# power_electronics2.net
KiCad netlist of a schematic drawn in EAGLE
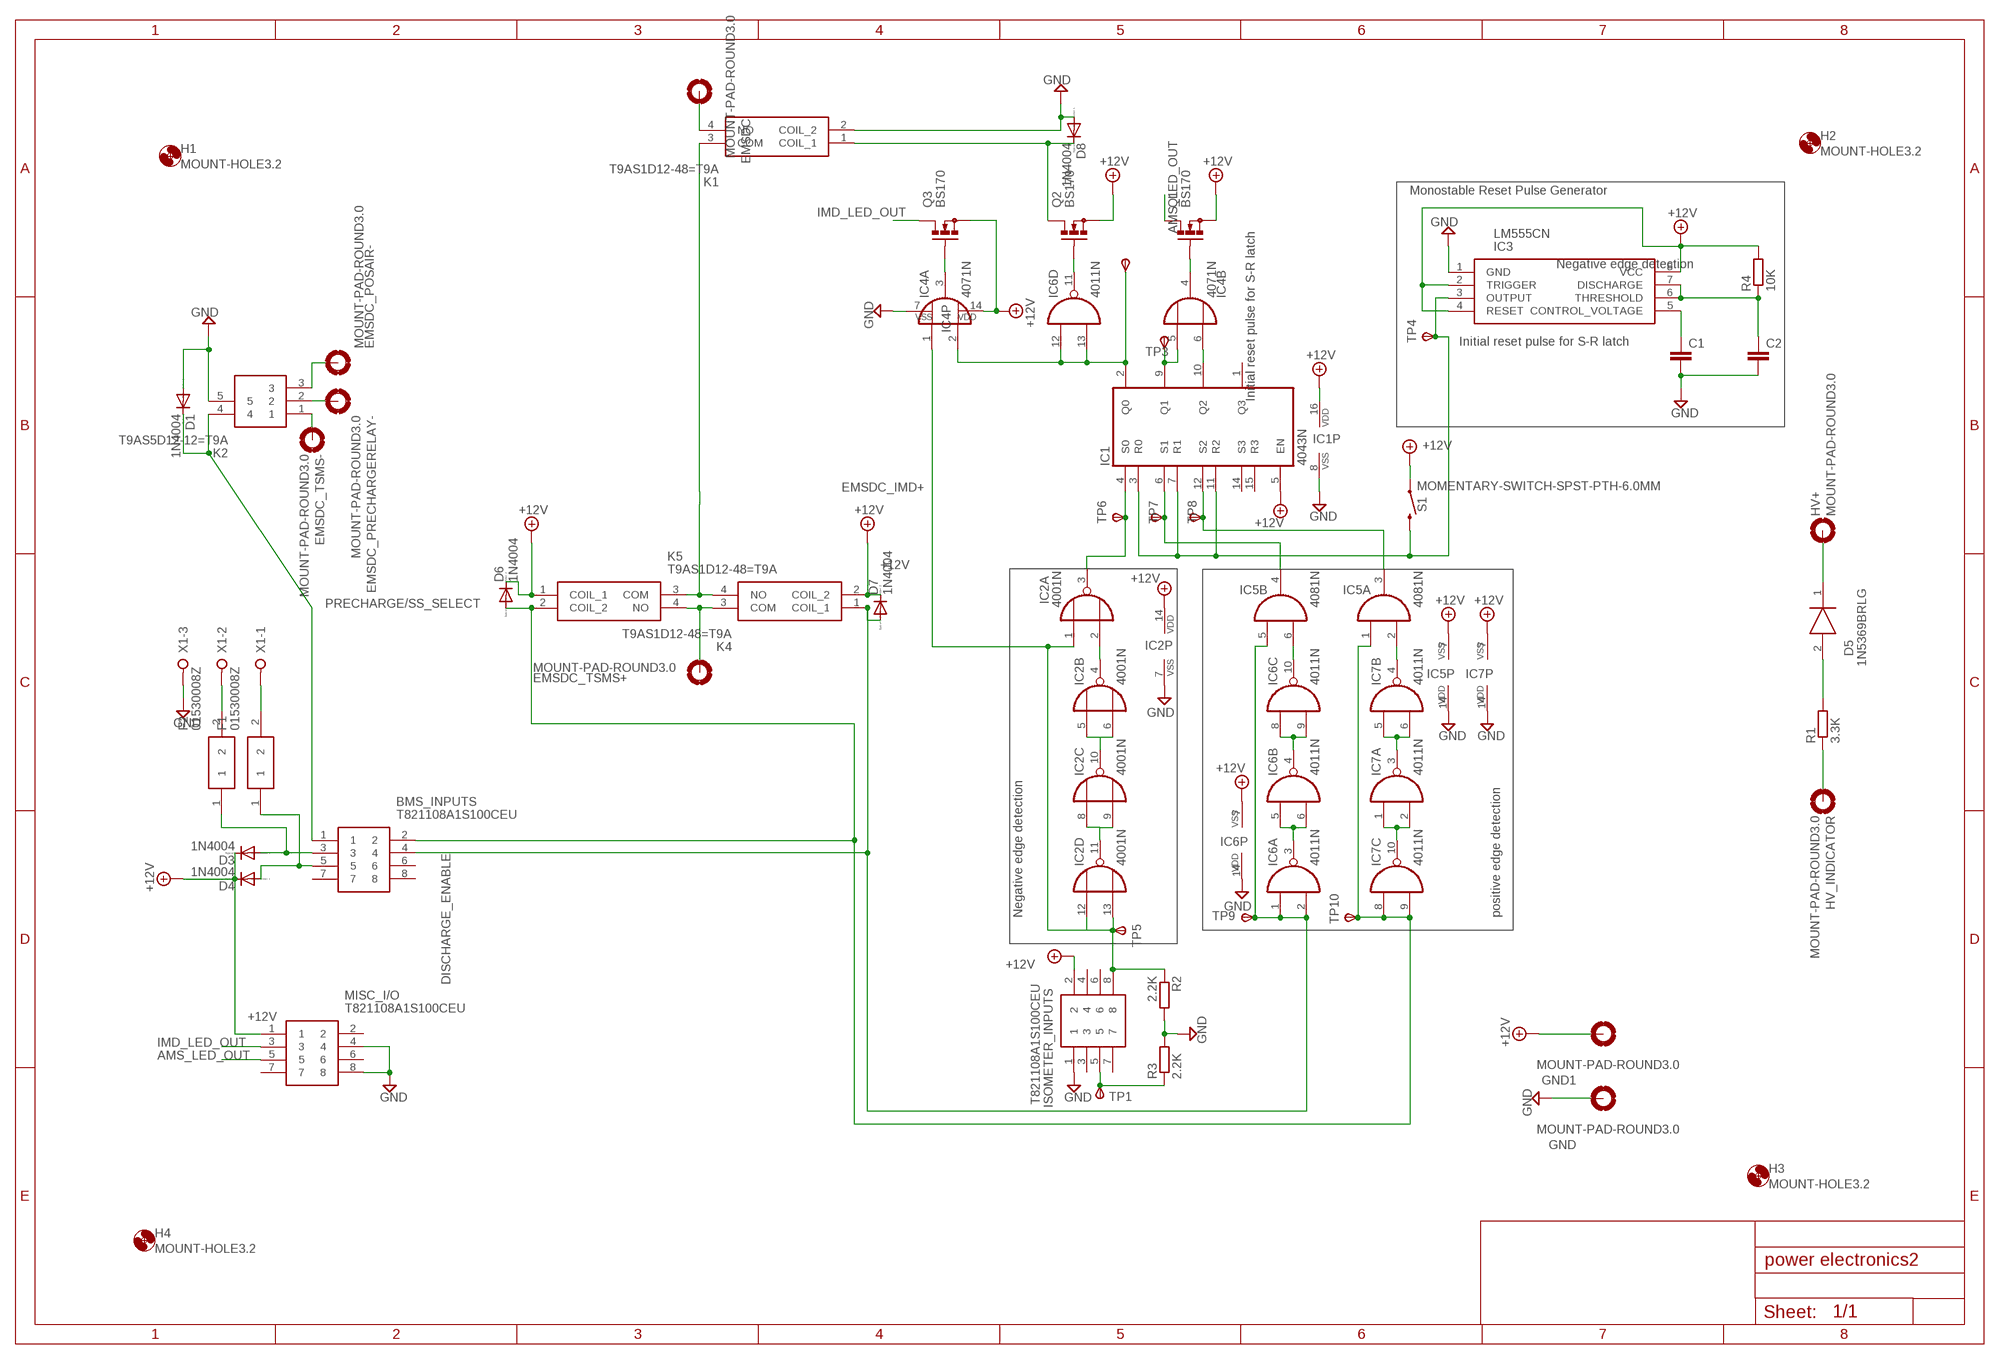
[diagram p0: schematic, sheet 1]

(export (version "E")
  (design (tool "Eeschema 10.0.6"))
  (components
    (comp (ref "BMS_INPUTS")
      (value "T821108A1S100CEU")
      (footprint "eagle-import:HDRV8W64P254_2X4_1778X895X915P")
      (fields (field (name "RS_PART_NUMBER") "8323569"))
      (libsource (lib "eagle-import") (part "T821108A1S100CEU"))
    )
    (comp (ref "C1")
      (value "C-EU050-024X044")
      (footprint "eagle-import:C050-024X044")
      (libsource (lib "eagle-import") (part "C-EU050-024X044"))
    )
    (comp (ref "C2")
      (value "C-EU050-024X044")
      (footprint "eagle-import:C050-024X044")
      (libsource (lib "eagle-import") (part "C-EU050-024X044"))
    )
    (comp (ref "D1")
      (value "1N4004")
      (footprint "eagle-import:DO41-10")
      (libsource (lib "eagle-import") (part "1N4004"))
    )
    (comp (ref "D3")
      (value "1N4004")
      (footprint "eagle-import:DO41-10")
      (libsource (lib "eagle-import") (part "1N4004"))
    )
    (comp (ref "D4")
      (value "1N4004")
      (footprint "eagle-import:DO41-10")
      (libsource (lib "eagle-import") (part "1N4004"))
    )
    (comp (ref "D5")
      (value "1N5369BRLG")
      (footprint "eagle-import:DIOAD2260W109L864D349")
      (fields (field (name "RS_PART_NUMBER") "6547678P"))
      (libsource (lib "eagle-import") (part "1N5369BRLG"))
    )
    (comp (ref "D6")
      (value "1N4004")
      (footprint "eagle-import:DO41-10")
      (libsource (lib "eagle-import") (part "1N4004"))
    )
    (comp (ref "D7")
      (value "1N4004")
      (footprint "eagle-import:DO41-10")
      (libsource (lib "eagle-import") (part "1N4004"))
    )
    (comp (ref "D8")
      (value "1N4004")
      (footprint "eagle-import:DO41-10")
      (libsource (lib "eagle-import") (part "1N4004"))
    )
    (comp (ref "EMSDC")
      (value "MOUNT-PAD-ROUND3.0")
      (footprint "eagle-import:3,0-PAD")
      (libsource (lib "eagle-import") (part "MOUNT-PAD-ROUND3.0"))
    )
    (comp (ref "EMSDC_POSAIR-")
      (value "MOUNT-PAD-ROUND3.0")
      (footprint "eagle-import:3,0-PAD")
      (libsource (lib "eagle-import") (part "MOUNT-PAD-ROUND3.0"))
    )
    (comp (ref "EMSDC_PRECHARGERELAY-")
      (value "MOUNT-PAD-ROUND3.0")
      (footprint "eagle-import:3,0-PAD")
      (libsource (lib "eagle-import") (part "MOUNT-PAD-ROUND3.0"))
    )
    (comp (ref "EMSDC_TSMS+")
      (value "MOUNT-PAD-ROUND3.0")
      (footprint "eagle-import:3,0-PAD")
      (libsource (lib "eagle-import") (part "MOUNT-PAD-ROUND3.0"))
    )
    (comp (ref "EMSDC_TSMS-")
      (value "MOUNT-PAD-ROUND3.0")
      (footprint "eagle-import:3,0-PAD")
      (libsource (lib "eagle-import") (part "MOUNT-PAD-ROUND3.0"))
    )
    (comp (ref "F1")
      (value "01530008Z")
      (footprint "eagle-import:01530008")
      (fields (field (name "RS_PART_NUMBER") "3607317"))
      (libsource (lib "eagle-import") (part "01530008Z"))
    )
    (comp (ref "F2")
      (value "01530008Z")
      (footprint "eagle-import:01530008")
      (fields (field (name "RS_PART_NUMBER") "3607317"))
      (libsource (lib "eagle-import") (part "01530008Z"))
    )
    (comp (ref "GND")
      (value "MOUNT-PAD-ROUND3.0")
      (footprint "eagle-import:3,0-PAD")
      (libsource (lib "eagle-import") (part "MOUNT-PAD-ROUND3.0"))
    )
    (comp (ref "GND1")
      (value "MOUNT-PAD-ROUND3.0")
      (footprint "eagle-import:3,0-PAD")
      (libsource (lib "eagle-import") (part "MOUNT-PAD-ROUND3.0"))
    )
    (comp (ref "H1")
      (value "MOUNT-HOLE3.2")
      (footprint "eagle-import:3,2")
      (libsource (lib "eagle-import") (part "MOUNT-HOLE3.2"))
    )
    (comp (ref "H2")
      (value "MOUNT-HOLE3.2")
      (footprint "eagle-import:3,2")
      (libsource (lib "eagle-import") (part "MOUNT-HOLE3.2"))
    )
    (comp (ref "H3")
      (value "MOUNT-HOLE3.2")
      (footprint "eagle-import:3,2")
      (libsource (lib "eagle-import") (part "MOUNT-HOLE3.2"))
    )
    (comp (ref "H4")
      (value "MOUNT-HOLE3.2")
      (footprint "eagle-import:3,2")
      (libsource (lib "eagle-import") (part "MOUNT-HOLE3.2"))
    )
    (comp (ref "HV+")
      (value "MOUNT-PAD-ROUND3.0")
      (footprint "eagle-import:3,0-PAD")
      (libsource (lib "eagle-import") (part "MOUNT-PAD-ROUND3.0"))
    )
    (comp (ref "HV_INDICATOR")
      (value "MOUNT-PAD-ROUND3.0")
      (footprint "eagle-import:3,0-PAD")
      (libsource (lib "eagle-import") (part "MOUNT-PAD-ROUND3.0"))
    )
    (comp (ref "IC1")
      (value "4043N")
      (footprint "eagle-import:DIL16")
      (libsource (lib "eagle-import") (part "4043N"))
    )
    (comp (ref "IC2")
      (value "4001N")
      (footprint "eagle-import:DIL14")
      (libsource (lib "eagle-import") (part "4001N"))
    )
    (comp (ref "IC3")
      (value "LM555CN")
      (footprint "eagle-import:DIP762W53P254L980H533Q8N")
      (fields (field (name "MOUSER_PART_NUMBER") "512-LM555CN"))
      (libsource (lib "eagle-import") (part "LM555CN"))
    )
    (comp (ref "IC4")
      (value "4071N")
      (footprint "eagle-import:DIL14")
      (libsource (lib "eagle-import") (part "4071N"))
    )
    (comp (ref "IC5")
      (value "4081N")
      (footprint "eagle-import:DIL14")
      (libsource (lib "eagle-import") (part "4081N"))
    )
    (comp (ref "IC6")
      (value "4011N")
      (footprint "eagle-import:DIL14")
      (libsource (lib "eagle-import") (part "4011N"))
    )
    (comp (ref "IC7")
      (value "4011N")
      (footprint "eagle-import:DIL14")
      (libsource (lib "eagle-import") (part "4011N"))
    )
    (comp (ref "ISOMETER_INPUTS")
      (value "T821108A1S100CEU")
      (footprint "eagle-import:HDRV8W64P254_2X4_1778X895X915P")
      (fields (field (name "RS_PART_NUMBER") "8323569"))
      (libsource (lib "eagle-import") (part "T821108A1S100CEU"))
    )
    (comp (ref "K1")
      (value "T9AS1D12-48=T9A")
      (footprint "eagle-import:T9AS1D1248T9A")
      (fields (field (name "RS_PART_NUMBER") "6802534P"))
      (libsource (lib "eagle-import") (part "T9AS1D12-48=T9A"))
    )
    (comp (ref "K2")
      (value "T9AS5D12-12=T9A")
      (footprint "eagle-import:T9AS1D12")
      (fields (field (name "RS_PART_NUMBER") "6802528"))
      (libsource (lib "eagle-import") (part "T9AS5D12-12=T9A"))
    )
    (comp (ref "K4")
      (value "T9AS1D12-48=T9A")
      (footprint "eagle-import:T9AS1D1248T9A")
      (fields (field (name "RS_PART_NUMBER") "6802534P"))
      (libsource (lib "eagle-import") (part "T9AS1D12-48=T9A"))
    )
    (comp (ref "K5")
      (value "T9AS1D12-48=T9A")
      (footprint "eagle-import:T9AS1D1248T9A")
      (fields (field (name "RS_PART_NUMBER") "6802534P"))
      (libsource (lib "eagle-import") (part "T9AS1D12-48=T9A"))
    )
    (comp (ref "MISC_I/O")
      (value "T821108A1S100CEU")
      (footprint "eagle-import:HDRV8W64P254_2X4_1778X895X915P")
      (fields (field (name "RS_PART_NUMBER") "8323569"))
      (libsource (lib "eagle-import") (part "T821108A1S100CEU"))
    )
    (comp (ref "Q1")
      (value "BS170")
      (footprint "eagle-import:SOT54E")
      (libsource (lib "eagle-import") (part "BS170"))
    )
    (comp (ref "Q2")
      (value "BS170")
      (footprint "eagle-import:SOT54E")
      (libsource (lib "eagle-import") (part "BS170"))
    )
    (comp (ref "Q3")
      (value "BS170")
      (footprint "eagle-import:SOT54E")
      (libsource (lib "eagle-import") (part "BS170"))
    )
    (comp (ref "R1")
      (value "3.3K")
      (footprint "eagle-import:0207_15")
      (libsource (lib "eagle-import") (part "R-EU_0207/15"))
    )
    (comp (ref "R2")
      (value "2.2K")
      (footprint "eagle-import:0207_12")
      (libsource (lib "eagle-import") (part "R-EU_0207/12"))
    )
    (comp (ref "R3")
      (value "2.2K")
      (footprint "eagle-import:0207_12")
      (libsource (lib "eagle-import") (part "R-EU_0207/12"))
    )
    (comp (ref "R4")
      (value "10K")
      (footprint "eagle-import:0207_15")
      (libsource (lib "eagle-import") (part "R-EU_0207/15"))
    )
    (comp (ref "S1")
      (value "MOMENTARY-SWITCH-SPST-PTH-6.0MM")
      (footprint "eagle-import:TACTILE_SWITCH_PTH_6.0MM")
      (libsource (lib "eagle-import") (part "MOMENTARY-SWITCH-SPST-PTH-6.0MM"))
    )
    (comp (ref "TP1")
      (value "TPSPAD1-17")
      (footprint "eagle-import:P1-17")
      (libsource (lib "eagle-import") (part "TPSPAD1-17"))
    )
    (comp (ref "TP2")
      (value "TPSPAD1-17")
      (footprint "eagle-import:P1-17")
      (libsource (lib "eagle-import") (part "TPSPAD1-17"))
    )
    (comp (ref "TP3")
      (value "TPSPAD1-17")
      (footprint "eagle-import:P1-17")
      (libsource (lib "eagle-import") (part "TPSPAD1-17"))
    )
    (comp (ref "TP4")
      (value "TPSPAD1-17")
      (footprint "eagle-import:P1-17")
      (libsource (lib "eagle-import") (part "TPSPAD1-17"))
    )
    (comp (ref "TP5")
      (value "TPSPAD1-17")
      (footprint "eagle-import:P1-17")
      (libsource (lib "eagle-import") (part "TPSPAD1-17"))
    )
    (comp (ref "TP6")
      (value "TPSPAD1-17")
      (footprint "eagle-import:P1-17")
      (libsource (lib "eagle-import") (part "TPSPAD1-17"))
    )
    (comp (ref "TP7")
      (value "TPSPAD1-17")
      (footprint "eagle-import:P1-17")
      (libsource (lib "eagle-import") (part "TPSPAD1-17"))
    )
    (comp (ref "TP8")
      (value "TPSPAD1-17")
      (footprint "eagle-import:P1-17")
      (libsource (lib "eagle-import") (part "TPSPAD1-17"))
    )
    (comp (ref "TP9")
      (value "TPSPAD1-17")
      (footprint "eagle-import:P1-17")
      (libsource (lib "eagle-import") (part "TPSPAD1-17"))
    )
    (comp (ref "TP10")
      (value "TPSPAD1-17")
      (footprint "eagle-import:P1-17")
      (libsource (lib "eagle-import") (part "TPSPAD1-17"))
    )
    (comp (ref "X1")
      (value "W237-3E")
      (footprint "eagle-import:W237-3E")
      (libsource (lib "eagle-import") (part "W237-3E"))
    )
  )
  (nets
    (net (code "1") (name "+12V") (class "Default")
      (node (ref "D3") (pin "C") (pinfunction "C_C") (pintype "passive"))
      (node (ref "D4") (pin "C") (pinfunction "C_C") (pintype "passive"))
      (node (ref "D6") (pin "C") (pinfunction "C_C") (pintype "passive"))
      (node (ref "D7") (pin "C") (pinfunction "C_C") (pintype "passive"))
      (node (ref "GND1") (pin "B3,0") (pinfunction "MOUNT_B3,0") (pintype "passive"))
      (node (ref "IC1") (pin "16") (pinfunction "VDD_16") (pintype "power_in"))
      (node (ref "IC1") (pin "5") (pinfunction "EN_5") (pintype "input"))
      (node (ref "IC2") (pin "14") (pinfunction "VDD_14") (pintype "power_in"))
      (node (ref "IC3") (pin "2") (pinfunction "TRIGGER_2") (pintype "bidirectional"))
      (node (ref "IC3") (pin "4") (pinfunction "RESET_4") (pintype "bidirectional"))
      (node (ref "IC3") (pin "8") (pinfunction "VCC_8") (pintype "bidirectional"))
      (node (ref "IC4") (pin "14") (pinfunction "VDD_14") (pintype "power_in"))
      (node (ref "IC5") (pin "7") (pinfunction "VSS_7") (pintype "power_in"))
      (node (ref "IC6") (pin "7") (pinfunction "VSS_7") (pintype "power_in"))
      (node (ref "IC7") (pin "7") (pinfunction "VSS_7") (pintype "power_in"))
      (node (ref "ISOMETER_INPUTS") (pin "2") (pinfunction "2_2") (pintype "bidirectional"))
      (node (ref "K4") (pin "2") (pinfunction "COIL_2_2") (pintype "bidirectional"))
      (node (ref "K5") (pin "1") (pinfunction "COIL_1_1") (pintype "bidirectional"))
      (node (ref "MISC_I/O") (pin "1") (pinfunction "1_1") (pintype "bidirectional"))
      (node (ref "Q1") (pin "S") (pinfunction "S_S") (pintype "passive"))
      (node (ref "Q2") (pin "S") (pinfunction "S_S") (pintype "passive"))
      (node (ref "Q3") (pin "S") (pinfunction "S_S") (pintype "passive"))
      (node (ref "R4") (pin "2") (pinfunction "2_2") (pintype "passive"))
      (node (ref "S1") (pin "1") (pinfunction "1_1") (pintype "passive"))
    )
    (net (code "2") (name "/AMS_LED_OUT") (class "Default")
      (node (ref "MISC_I/O") (pin "5") (pinfunction "5_5") (pintype "bidirectional"))
      (node (ref "Q1") (pin "D") (pinfunction "D_D") (pintype "passive"))
    )
    (net (code "3") (name "/DISCHARGE_ENABLE") (class "Default")
      (node (ref "BMS_INPUTS") (pin "4") (pinfunction "4_4") (pintype "bidirectional"))
      (node (ref "D7") (pin "A") (pinfunction "A_A") (pintype "passive"))
      (node (ref "IC5") (pin "5") (pinfunction "I0_5") (pintype "input"))
      (node (ref "IC6") (pin "1") (pinfunction "I0_1") (pintype "input"))
      (node (ref "IC6") (pin "2") (pinfunction "I1_2") (pintype "input"))
      (node (ref "K4") (pin "1") (pinfunction "COIL_1_1") (pintype "bidirectional"))
      (node (ref "TP9") (pin "TP") (pinfunction "PP_TP") (pintype "input"))
    )
    (net (code "4") (name "/EMSDC_IMD+") (class "Default")
      (node (ref "K1") (pin "3") (pinfunction "COM_3") (pintype "bidirectional"))
      (node (ref "K4") (pin "4") (pinfunction "NO_4") (pintype "bidirectional"))
      (node (ref "K5") (pin "3") (pinfunction "COM_3") (pintype "bidirectional"))
    )
    (net (code "5") (name "/IMD_LED_OUT") (class "Default")
      (node (ref "MISC_I/O") (pin "3") (pinfunction "3_3") (pintype "bidirectional"))
      (node (ref "Q3") (pin "D") (pinfunction "D_D") (pintype "passive"))
    )
    (net (code "6") (name "/PRECHARGE{slash}SS_SELECT") (class "Default")
      (node (ref "BMS_INPUTS") (pin "1") (pinfunction "1_1") (pintype "bidirectional"))
      (node (ref "D1") (pin "C") (pinfunction "C_C") (pintype "passive"))
      (node (ref "K2") (pin "4") (pinfunction "4_4") (pintype "bidirectional"))
    )
    (net (code "7") (name "GND") (class "Default")
      (node (ref "C1") (pin "2") (pinfunction "2_2") (pintype "passive"))
      (node (ref "C2") (pin "2") (pinfunction "2_2") (pintype "passive"))
      (node (ref "D1") (pin "A") (pinfunction "A_A") (pintype "passive"))
      (node (ref "D8") (pin "A") (pinfunction "A_A") (pintype "passive"))
      (node (ref "GND") (pin "B3,0") (pinfunction "MOUNT_B3,0") (pintype "passive"))
      (node (ref "IC1") (pin "8") (pinfunction "VSS_8") (pintype "power_in"))
      (node (ref "IC2") (pin "7") (pinfunction "VSS_7") (pintype "power_in"))
      (node (ref "IC3") (pin "1") (pinfunction "GND_1") (pintype "bidirectional"))
      (node (ref "IC4") (pin "7") (pinfunction "VSS_7") (pintype "power_in"))
      (node (ref "IC5") (pin "14") (pinfunction "VDD_14") (pintype "power_in"))
      (node (ref "IC6") (pin "14") (pinfunction "VDD_14") (pintype "power_in"))
      (node (ref "IC7") (pin "14") (pinfunction "VDD_14") (pintype "power_in"))
      (node (ref "ISOMETER_INPUTS") (pin "1") (pinfunction "1_1") (pintype "bidirectional"))
      (node (ref "K1") (pin "2") (pinfunction "COIL_2_2") (pintype "bidirectional"))
      (node (ref "K2") (pin "5") (pinfunction "5_5") (pintype "bidirectional"))
      (node (ref "MISC_I/O") (pin "4") (pinfunction "4_4") (pintype "bidirectional"))
      (node (ref "MISC_I/O") (pin "8") (pinfunction "8_8") (pintype "bidirectional"))
      (node (ref "R2") (pin "2") (pinfunction "2_2") (pintype "passive"))
      (node (ref "R3") (pin "2") (pinfunction "2_2") (pintype "passive"))
      (node (ref "X1") (pin "3") (pinfunction "KL_3") (pintype "passive"))
    )
    (net (code "8") (name "Net-(BMS_INPUTS-Pad3)") (class "Default")
      (node (ref "BMS_INPUTS") (pin "3") (pinfunction "3_3") (pintype "bidirectional"))
      (node (ref "D3") (pin "A") (pinfunction "A_A") (pintype "passive"))
      (node (ref "F2") (pin "1") (pinfunction "1_1") (pintype "bidirectional"))
    )
    (net (code "9") (name "Net-(BMS_INPUTS-Pad5)") (class "Default")
      (node (ref "BMS_INPUTS") (pin "5") (pinfunction "5_5") (pintype "bidirectional"))
      (node (ref "D4") (pin "A") (pinfunction "A_A") (pintype "passive"))
      (node (ref "F1") (pin "1") (pinfunction "1_1") (pintype "bidirectional"))
    )
    (net (code "10") (name "Net-(D5-A)") (class "Default")
      (node (ref "D5") (pin "2") (pinfunction "A_2") (pintype "bidirectional"))
      (node (ref "R1") (pin "2") (pinfunction "2_2") (pintype "passive"))
    )
    (net (code "11") (name "Net-(D5-K)") (class "Default")
      (node (ref "D5") (pin "1") (pinfunction "K_1") (pintype "bidirectional"))
      (node (ref "HV+") (pin "B3,0") (pinfunction "MOUNT_B3,0") (pintype "passive"))
    )
    (net (code "12") (name "Net-(EMSDC-MOUNT)") (class "Default")
      (node (ref "EMSDC") (pin "B3,0") (pinfunction "MOUNT_B3,0") (pintype "passive"))
      (node (ref "K1") (pin "4") (pinfunction "NO_4") (pintype "bidirectional"))
    )
    (net (code "13") (name "Net-(EMSDC_POSAIR--MOUNT)") (class "Default")
      (node (ref "EMSDC_POSAIR-") (pin "B3,0") (pinfunction "MOUNT_B3,0") (pintype "passive"))
      (node (ref "K2") (pin "3") (pinfunction "3_3") (pintype "bidirectional"))
    )
    (net (code "14") (name "Net-(EMSDC_PRECHARGERELAY--MOUNT)") (class "Default")
      (node (ref "EMSDC_PRECHARGERELAY-") (pin "B3,0") (pinfunction "MOUNT_B3,0") (pintype "passive"))
      (node (ref "K2") (pin "2") (pinfunction "2_2") (pintype "bidirectional"))
    )
    (net (code "15") (name "Net-(EMSDC_TSMS+-MOUNT)") (class "Default")
      (node (ref "EMSDC_TSMS+") (pin "B3,0") (pinfunction "MOUNT_B3,0") (pintype "passive"))
      (node (ref "K4") (pin "3") (pinfunction "COM_3") (pintype "bidirectional"))
      (node (ref "K5") (pin "4") (pinfunction "NO_4") (pintype "bidirectional"))
    )
    (net (code "16") (name "Net-(EMSDC_TSMS--MOUNT)") (class "Default")
      (node (ref "EMSDC_TSMS-") (pin "B3,0") (pinfunction "MOUNT_B3,0") (pintype "passive"))
      (node (ref "K2") (pin "1") (pinfunction "1_1") (pintype "bidirectional"))
    )
    (net (code "17") (name "Net-(HV_INDICATOR-MOUNT)") (class "Default")
      (node (ref "HV_INDICATOR") (pin "B3,0") (pinfunction "MOUNT_B3,0") (pintype "passive"))
      (node (ref "R1") (pin "1") (pinfunction "1_1") (pintype "passive"))
    )
    (net (code "18") (name "Net-(IC1A-Q0)") (class "Default")
      (node (ref "IC1") (pin "2") (pinfunction "Q0_2") (pintype "output"))
      (node (ref "IC4") (pin "2") (pinfunction "I1_2") (pintype "input"))
      (node (ref "IC6") (pin "12") (pinfunction "I0_12") (pintype "input"))
      (node (ref "IC6") (pin "13") (pinfunction "I1_13") (pintype "input"))
      (node (ref "TP2") (pin "TP") (pinfunction "PP_TP") (pintype "input"))
    )
    (net (code "19") (name "Net-(IC1A-Q1)") (class "Default")
      (node (ref "IC1") (pin "9") (pinfunction "Q1_9") (pintype "output"))
      (node (ref "IC4") (pin "5") (pinfunction "I0_5") (pintype "input"))
      (node (ref "TP3") (pin "TP") (pinfunction "PP_TP") (pintype "input"))
    )
    (net (code "20") (name "Net-(IC1A-Q2)") (class "Default")
      (node (ref "IC1") (pin "10") (pinfunction "Q2_10") (pintype "output"))
      (node (ref "IC4") (pin "6") (pinfunction "I1_6") (pintype "input"))
    )
    (net (code "21") (name "Net-(IC1A-R0)") (class "Default")
      (node (ref "IC1") (pin "11") (pinfunction "R2_11") (pintype "input"))
      (node (ref "IC1") (pin "3") (pinfunction "R0_3") (pintype "input"))
      (node (ref "IC1") (pin "7") (pinfunction "R1_7") (pintype "input"))
      (node (ref "IC3") (pin "3") (pinfunction "OUTPUT_3") (pintype "bidirectional"))
      (node (ref "S1") (pin "3") (pinfunction "2_3") (pintype "passive"))
      (node (ref "TP4") (pin "TP") (pinfunction "PP_TP") (pintype "input"))
    )
    (net (code "22") (name "Net-(IC1A-S0)") (class "Default")
      (node (ref "IC1") (pin "4") (pinfunction "S0_4") (pintype "input"))
      (node (ref "IC2") (pin "3") (pinfunction "O_3") (pintype "output"))
      (node (ref "TP6") (pin "TP") (pinfunction "PP_TP") (pintype "input"))
    )
    (net (code "23") (name "Net-(IC1A-S1)") (class "Default")
      (node (ref "IC1") (pin "6") (pinfunction "S1_6") (pintype "input"))
      (node (ref "IC5") (pin "4") (pinfunction "O_4") (pintype "output"))
      (node (ref "TP7") (pin "TP") (pinfunction "PP_TP") (pintype "input"))
    )
    (net (code "24") (name "Net-(IC1A-S2)") (class "Default")
      (node (ref "IC1") (pin "12") (pinfunction "S2_12") (pintype "input"))
      (node (ref "IC5") (pin "3") (pinfunction "O_3") (pintype "output"))
      (node (ref "TP8") (pin "TP") (pinfunction "PP_TP") (pintype "input"))
    )
    (net (code "25") (name "Net-(IC2A-I0)") (class "Default")
      (node (ref "IC2") (pin "1") (pinfunction "I0_1") (pintype "input"))
      (node (ref "IC2") (pin "12") (pinfunction "I0_12") (pintype "input"))
      (node (ref "IC2") (pin "13") (pinfunction "I1_13") (pintype "input"))
      (node (ref "IC4") (pin "1") (pinfunction "I0_1") (pintype "input"))
      (node (ref "ISOMETER_INPUTS") (pin "8") (pinfunction "8_8") (pintype "bidirectional"))
      (node (ref "R2") (pin "1") (pinfunction "1_1") (pintype "passive"))
      (node (ref "TP5") (pin "TP") (pinfunction "PP_TP") (pintype "input"))
    )
    (net (code "26") (name "Net-(IC2A-I1)") (class "Default")
      (node (ref "IC2") (pin "2") (pinfunction "I1_2") (pintype "input"))
      (node (ref "IC2") (pin "4") (pinfunction "O_4") (pintype "output"))
    )
    (net (code "27") (name "Net-(IC2B-I0)") (class "Default")
      (node (ref "IC2") (pin "10") (pinfunction "O_10") (pintype "output"))
      (node (ref "IC2") (pin "5") (pinfunction "I0_5") (pintype "input"))
      (node (ref "IC2") (pin "6") (pinfunction "I1_6") (pintype "input"))
    )
    (net (code "28") (name "Net-(IC2C-I0)") (class "Default")
      (node (ref "IC2") (pin "11") (pinfunction "O_11") (pintype "output"))
      (node (ref "IC2") (pin "8") (pinfunction "I0_8") (pintype "input"))
      (node (ref "IC2") (pin "9") (pinfunction "I1_9") (pintype "input"))
    )
    (net (code "29") (name "Net-(IC3-CONTROL_VOLTAGE)") (class "Default")
      (node (ref "C1") (pin "1") (pinfunction "1_1") (pintype "passive"))
      (node (ref "IC3") (pin "5") (pinfunction "CONTROL_VOLTAGE_5") (pintype "bidirectional"))
    )
    (net (code "30") (name "Net-(IC3-DISCHARGE)") (class "Default")
      (node (ref "C2") (pin "1") (pinfunction "1_1") (pintype "passive"))
      (node (ref "IC3") (pin "6") (pinfunction "THRESHOLD_6") (pintype "bidirectional"))
      (node (ref "IC3") (pin "7") (pinfunction "DISCHARGE_7") (pintype "bidirectional"))
      (node (ref "R4") (pin "1") (pinfunction "1_1") (pintype "passive"))
    )
    (net (code "31") (name "Net-(IC4A-O)") (class "Default")
      (node (ref "IC4") (pin "3") (pinfunction "O_3") (pintype "output"))
      (node (ref "Q3") (pin "G") (pinfunction "G_G") (pintype "passive"))
    )
    (net (code "32") (name "Net-(IC4B-O)") (class "Default")
      (node (ref "IC4") (pin "4") (pinfunction "O_4") (pintype "output"))
      (node (ref "Q1") (pin "G") (pinfunction "G_G") (pintype "passive"))
    )
    (net (code "33") (name "Net-(IC5A-I0)") (class "Default")
      (node (ref "IC5") (pin "1") (pinfunction "I0_1") (pintype "input"))
      (node (ref "IC7") (pin "8") (pinfunction "I0_8") (pintype "input"))
      (node (ref "TP10") (pin "TP") (pinfunction "PP_TP") (pintype "input"))
    )
    (net (code "34") (name "Net-(IC5A-I1)") (class "Default")
      (node (ref "IC5") (pin "2") (pinfunction "I1_2") (pintype "input"))
      (node (ref "IC7") (pin "4") (pinfunction "O_4") (pintype "output"))
    )
    (net (code "35") (name "Net-(IC5B-I1)") (class "Default")
      (node (ref "IC5") (pin "6") (pinfunction "I1_6") (pintype "input"))
      (node (ref "IC6") (pin "10") (pinfunction "O_10") (pintype "output"))
    )
    (net (code "36") (name "Net-(IC6A-O)") (class "Default")
      (node (ref "IC6") (pin "3") (pinfunction "O_3") (pintype "output"))
      (node (ref "IC6") (pin "5") (pinfunction "I0_5") (pintype "input"))
      (node (ref "IC6") (pin "6") (pinfunction "I1_6") (pintype "input"))
    )
    (net (code "37") (name "Net-(IC6B-O)") (class "Default")
      (node (ref "IC6") (pin "4") (pinfunction "O_4") (pintype "output"))
      (node (ref "IC6") (pin "8") (pinfunction "I0_8") (pintype "input"))
      (node (ref "IC6") (pin "9") (pinfunction "I1_9") (pintype "input"))
    )
    (net (code "38") (name "Net-(IC6D-O)") (class "Default")
      (node (ref "IC6") (pin "11") (pinfunction "O_11") (pintype "output"))
      (node (ref "Q2") (pin "G") (pinfunction "G_G") (pintype "passive"))
    )
    (net (code "39") (name "Net-(IC7A-I0)") (class "Default")
      (node (ref "IC7") (pin "1") (pinfunction "I0_1") (pintype "input"))
      (node (ref "IC7") (pin "10") (pinfunction "O_10") (pintype "output"))
      (node (ref "IC7") (pin "2") (pinfunction "I1_2") (pintype "input"))
    )
    (net (code "40") (name "Net-(IC7A-O)") (class "Default")
      (node (ref "IC7") (pin "3") (pinfunction "O_3") (pintype "output"))
      (node (ref "IC7") (pin "5") (pinfunction "I0_5") (pintype "input"))
      (node (ref "IC7") (pin "6") (pinfunction "I1_6") (pintype "input"))
    )
    (net (code "41") (name "Net-(IC7C-I1)") (class "Default")
      (node (ref "BMS_INPUTS") (pin "2") (pinfunction "2_2") (pintype "bidirectional"))
      (node (ref "D6") (pin "A") (pinfunction "A_A") (pintype "passive"))
      (node (ref "IC7") (pin "9") (pinfunction "I1_9") (pintype "input"))
      (node (ref "K5") (pin "2") (pinfunction "COIL_2_2") (pintype "bidirectional"))
    )
    (net (code "42") (name "Net-(K1-COIL_1)") (class "Default")
      (node (ref "D8") (pin "C") (pinfunction "C_C") (pintype "passive"))
      (node (ref "K1") (pin "1") (pinfunction "COIL_1_1") (pintype "bidirectional"))
      (node (ref "Q2") (pin "D") (pinfunction "D_D") (pintype "passive"))
    )
    (net (code "43") (name "Net-(TP1-PP)") (class "Default")
      (node (ref "ISOMETER_INPUTS") (pin "5") (pinfunction "5_5") (pintype "bidirectional"))
      (node (ref "R3") (pin "1") (pinfunction "1_1") (pintype "passive"))
      (node (ref "TP1") (pin "TP") (pinfunction "PP_TP") (pintype "input"))
    )
    (net (code "44") (name "Net-(X1A-KL)") (class "Default")
      (node (ref "F1") (pin "2") (pinfunction "2_2") (pintype "bidirectional"))
      (node (ref "X1") (pin "1") (pinfunction "KL_1") (pintype "passive"))
    )
    (net (code "45") (name "Net-(X1B-KL)") (class "Default")
      (node (ref "F2") (pin "2") (pinfunction "2_2") (pintype "bidirectional"))
      (node (ref "X1") (pin "2") (pinfunction "KL_2") (pintype "passive"))
    )
    (net (code "46") (name "unconnected-(BMS_INPUTS-Pad6)") (class "Default")
      (node (ref "BMS_INPUTS") (pin "6") (pinfunction "6_6") (pintype "bidirectional"))
    )
    (net (code "47") (name "unconnected-(BMS_INPUTS-Pad7)") (class "Default")
      (node (ref "BMS_INPUTS") (pin "7") (pinfunction "7_7") (pintype "bidirectional"))
    )
    (net (code "48") (name "unconnected-(BMS_INPUTS-Pad8)") (class "Default")
      (node (ref "BMS_INPUTS") (pin "8") (pinfunction "8_8") (pintype "bidirectional"))
    )
    (net (code "49") (name "unconnected-(IC1A-Q3-Pad1)") (class "Default")
      (node (ref "IC1") (pin "1") (pinfunction "Q3_1") (pintype "output"))
    )
    (net (code "50") (name "unconnected-(IC1A-R3-Pad15)") (class "Default")
      (node (ref "IC1") (pin "15") (pinfunction "R3_15") (pintype "input"))
    )
    (net (code "51") (name "unconnected-(IC1A-S3-Pad14)") (class "Default")
      (node (ref "IC1") (pin "14") (pinfunction "S3_14") (pintype "input"))
    )
    (net (code "52") (name "unconnected-(ISOMETER_INPUTS-Pad3)") (class "Default")
      (node (ref "ISOMETER_INPUTS") (pin "3") (pinfunction "3_3") (pintype "bidirectional"))
    )
    (net (code "53") (name "unconnected-(ISOMETER_INPUTS-Pad4)") (class "Default")
      (node (ref "ISOMETER_INPUTS") (pin "4") (pinfunction "4_4") (pintype "bidirectional"))
    )
    (net (code "54") (name "unconnected-(ISOMETER_INPUTS-Pad6)") (class "Default")
      (node (ref "ISOMETER_INPUTS") (pin "6") (pinfunction "6_6") (pintype "bidirectional"))
    )
    (net (code "55") (name "unconnected-(ISOMETER_INPUTS-Pad7)") (class "Default")
      (node (ref "ISOMETER_INPUTS") (pin "7") (pinfunction "7_7") (pintype "bidirectional"))
    )
    (net (code "56") (name "unconnected-(MISC_I/O-Pad2)") (class "Default")
      (node (ref "MISC_I/O") (pin "2") (pinfunction "2_2") (pintype "bidirectional"))
    )
    (net (code "57") (name "unconnected-(MISC_I/O-Pad6)") (class "Default")
      (node (ref "MISC_I/O") (pin "6") (pinfunction "6_6") (pintype "bidirectional"))
    )
    (net (code "58") (name "unconnected-(MISC_I/O-Pad7)") (class "Default")
      (node (ref "MISC_I/O") (pin "7") (pinfunction "7_7") (pintype "bidirectional"))
    )
  )
)
